# 2018_Dashboard.net
KiCad netlist of a schematic drawn in EAGLE
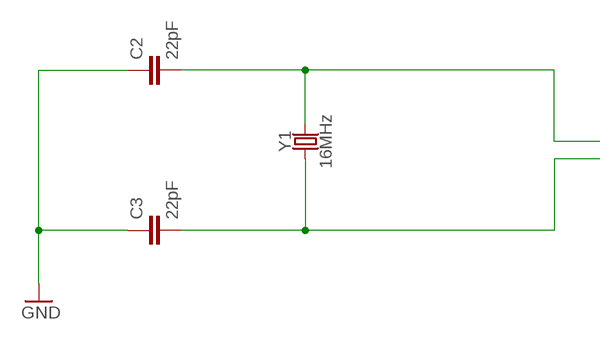
[diagram p0: schematic, sheet 1, part 1 of 2]
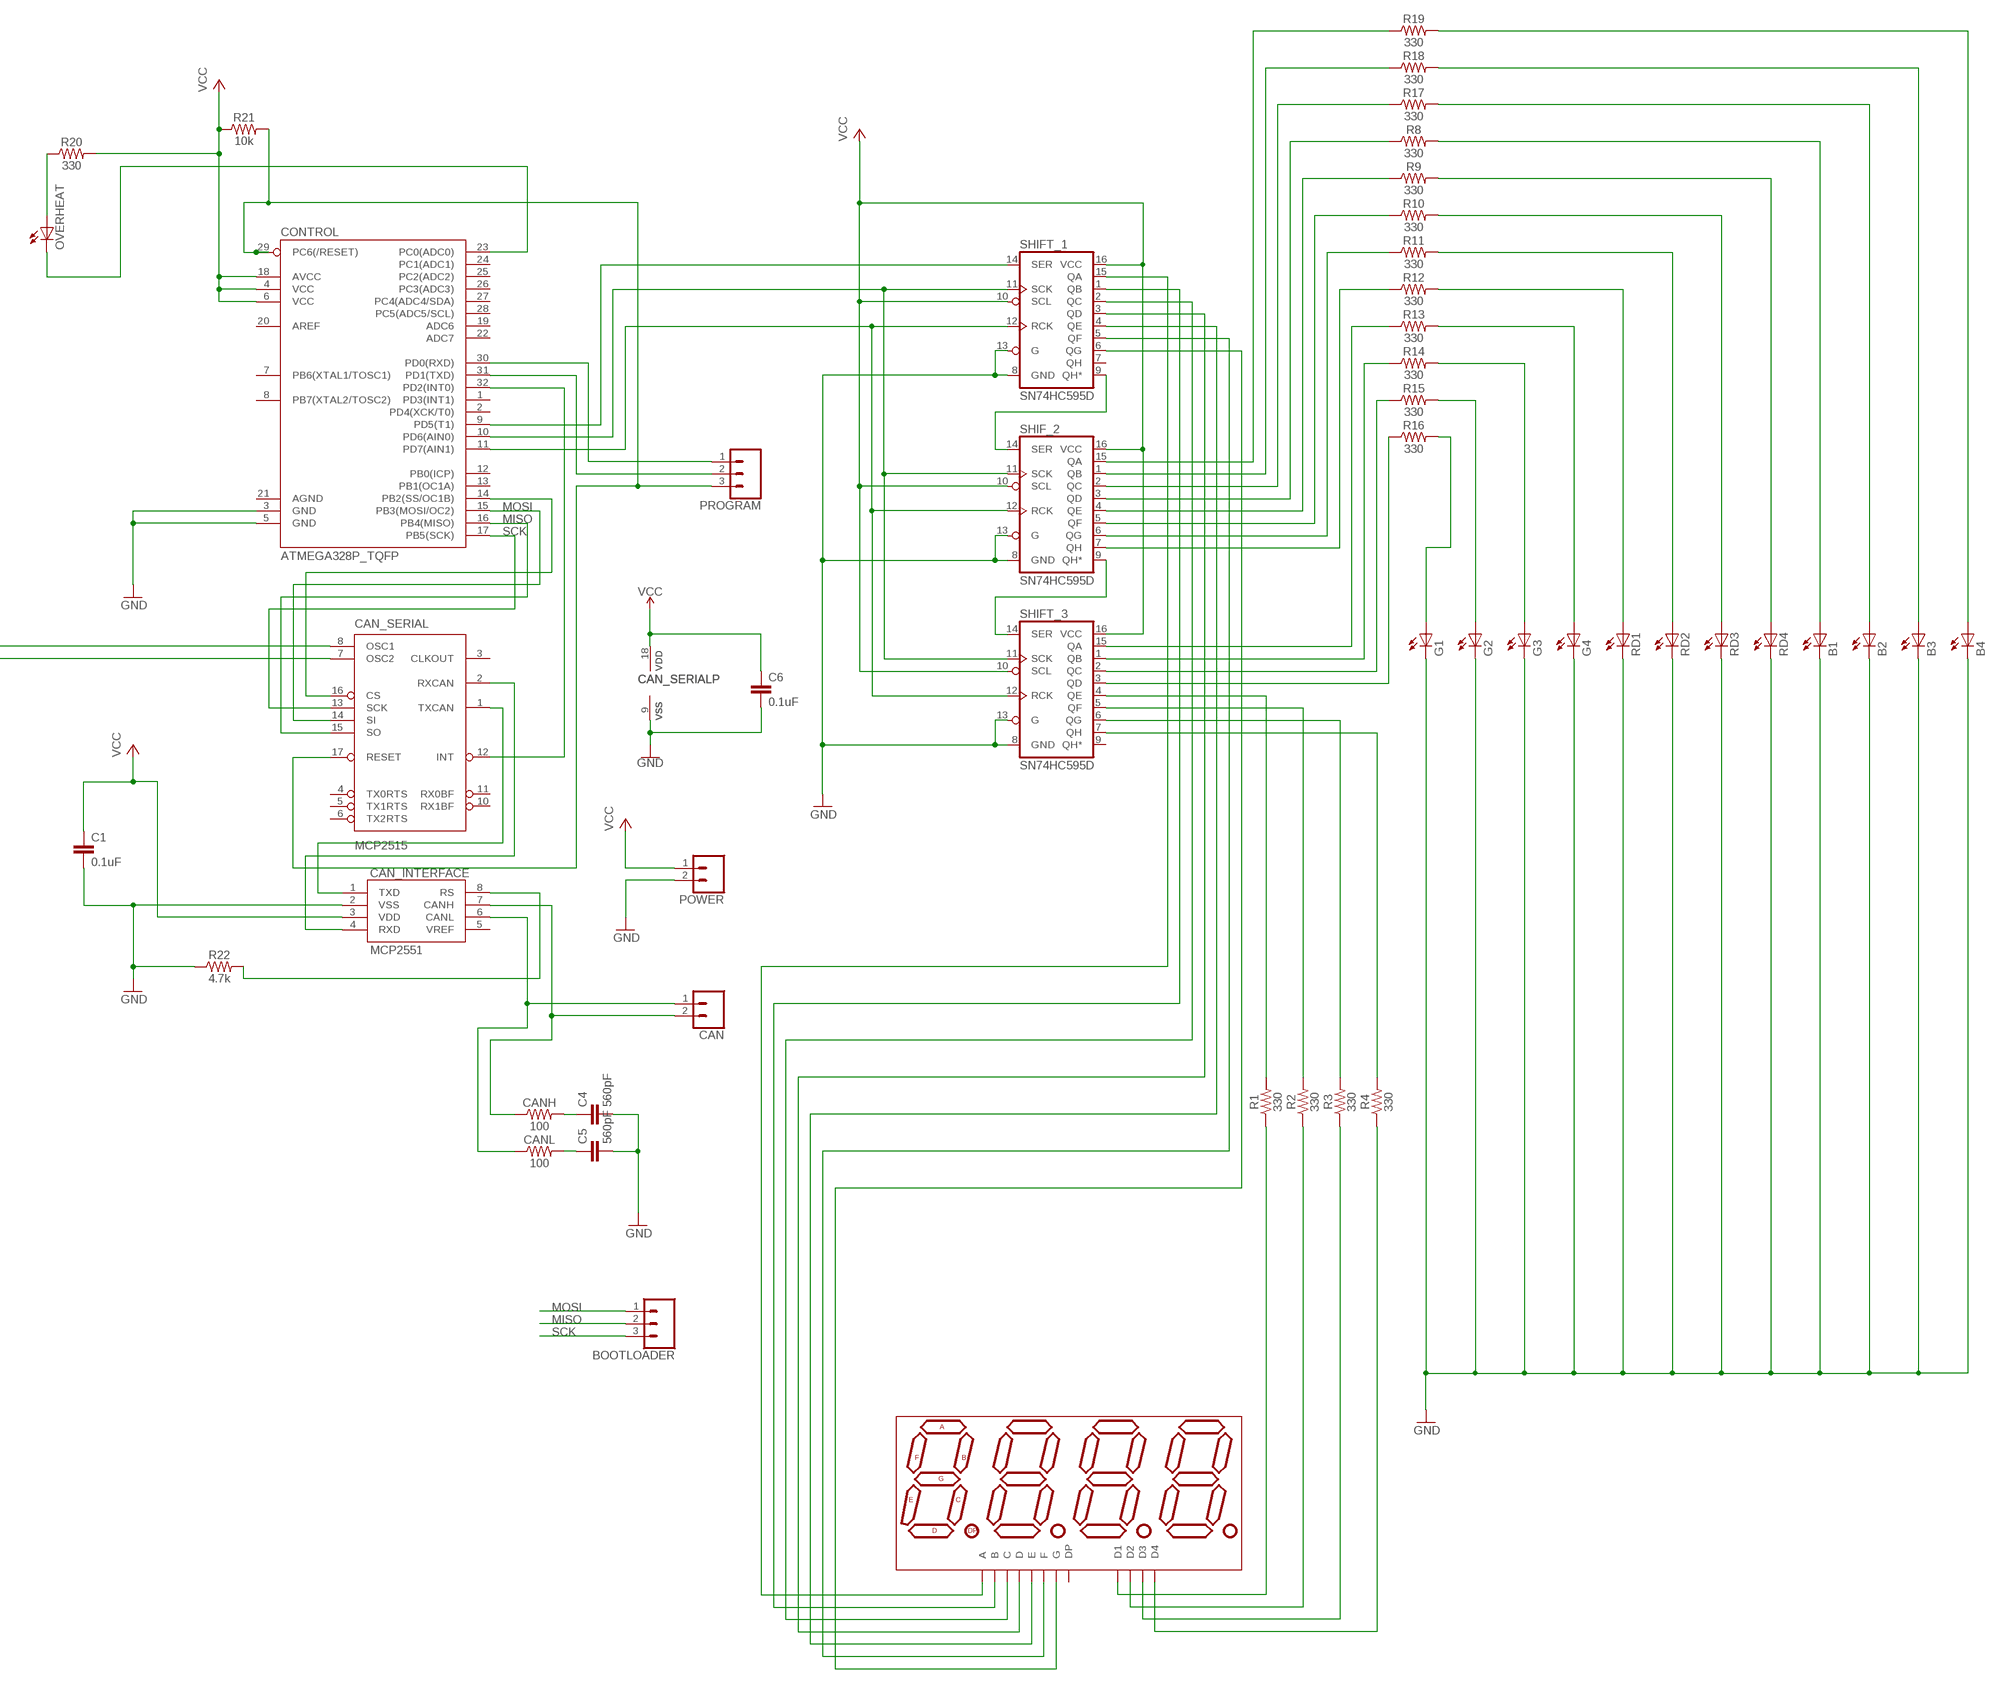
[diagram p1: schematic, sheet 1, part 2 of 2]

(export (version "E")
  (design (tool "Eeschema 10.0.6"))
  (components
    (comp (ref "B1")
      (value "TLLG4400")
      (footprint "eagle-import:LED3MM")
      (fields (field (name "MF") "VISHAY SEMICONDUCTOR"))
      (libsource (lib "eagle-import") (part "TLLG4400"))
    )
    (comp (ref "B2")
      (value "TLLG4400")
      (footprint "eagle-import:LED3MM")
      (fields (field (name "MF") "VISHAY SEMICONDUCTOR"))
      (libsource (lib "eagle-import") (part "TLLG4400"))
    )
    (comp (ref "B3")
      (value "TLLG4400")
      (footprint "eagle-import:LED3MM")
      (fields (field (name "MF") "VISHAY SEMICONDUCTOR"))
      (libsource (lib "eagle-import") (part "TLLG4400"))
    )
    (comp (ref "B4")
      (value "TLLG4400")
      (footprint "eagle-import:LED3MM")
      (fields (field (name "MF") "VISHAY SEMICONDUCTOR"))
      (libsource (lib "eagle-import") (part "TLLG4400"))
    )
    (comp (ref "BOOTLOADER")
      (value "CONN_03")
      (footprint "eagle-import:1X03")
      (libsource (lib "eagle-import") (part "CONN_03"))
    )
    (comp (ref "C1")
      (value "0.1uF")
      (footprint "eagle-import:0603")
      (libsource (lib "eagle-import") (part "0.1UF-0603-25V-(+80/-20%)"))
    )
    (comp (ref "C2")
      (value "22pF")
      (footprint "eagle-import:0603")
      (libsource (lib "eagle-import") (part "22PF-0603-50V-5%"))
    )
    (comp (ref "C3")
      (value "22pF")
      (footprint "eagle-import:0603")
      (libsource (lib "eagle-import") (part "22PF-0603-50V-5%"))
    )
    (comp (ref "C4")
      (value "560pF")
      (footprint "eagle-import:0603")
      (libsource (lib "eagle-import") (part "560PF-0603-50V-5%"))
    )
    (comp (ref "C5")
      (value "560pF")
      (footprint "eagle-import:0603")
      (libsource (lib "eagle-import") (part "560PF-0603-50V-5%"))
    )
    (comp (ref "C6")
      (value "0.1uF")
      (footprint "eagle-import:0402")
      (libsource (lib "eagle-import") (part "0.1UF-0402-16V-10%"))
    )
    (comp (ref "CAN")
      (value "CONN_02")
      (footprint "eagle-import:1X02")
      (libsource (lib "eagle-import") (part "CONN_02"))
    )
    (comp (ref "CANH")
      (value "100")
      (footprint "eagle-import:0603")
      (libsource (lib "eagle-import") (part "100OHM-0603-1/4W-5%"))
    )
    (comp (ref "CANL")
      (value "100")
      (footprint "eagle-import:0603")
      (libsource (lib "eagle-import") (part "100OHM-0603-1/4W-5%"))
    )
    (comp (ref "CAN_INTERFACE")
      (value "MCP2551")
      (footprint "eagle-import:SO08")
      (libsource (lib "eagle-import") (part "MCP2551"))
    )
    (comp (ref "CAN_SERIAL")
      (value "MCP2515")
      (footprint "eagle-import:SO18W")
      (libsource (lib "eagle-import") (part "MCP2515(MCP2510)SO"))
    )
    (comp (ref "CONTROL")
      (value "ATMEGA328P_TQFP")
      (footprint "eagle-import:TQFP32-08")
      (libsource (lib "eagle-import") (part "ATMEGA328P_TQFP"))
    )
    (comp (ref "G1")
      (value "TLLG4400")
      (footprint "eagle-import:LED3MM")
      (fields (field (name "MF") "VISHAY SEMICONDUCTOR"))
      (libsource (lib "eagle-import") (part "TLLG4400"))
    )
    (comp (ref "G2")
      (value "TLLG4400")
      (footprint "eagle-import:LED3MM")
      (fields (field (name "MF") "VISHAY SEMICONDUCTOR"))
      (libsource (lib "eagle-import") (part "TLLG4400"))
    )
    (comp (ref "G3")
      (value "TLLG4400")
      (footprint "eagle-import:LED3MM")
      (fields (field (name "MF") "VISHAY SEMICONDUCTOR"))
      (libsource (lib "eagle-import") (part "TLLG4400"))
    )
    (comp (ref "G4")
      (value "TLLG4400")
      (footprint "eagle-import:LED3MM")
      (fields (field (name "MF") "VISHAY SEMICONDUCTOR"))
      (libsource (lib "eagle-import") (part "TLLG4400"))
    )
    (comp (ref "OVERHEAT")
      (value "TLLG4400")
      (footprint "eagle-import:LED3MM")
      (fields (field (name "MF") "VISHAY SEMICONDUCTOR"))
      (libsource (lib "eagle-import") (part "TLLG4400"))
    )
    (comp (ref "POWER")
      (value "CONN_02")
      (footprint "eagle-import:1X02")
      (libsource (lib "eagle-import") (part "CONN_02"))
    )
    (comp (ref "PROGRAM")
      (value "CONN_03")
      (footprint "eagle-import:1X03")
      (libsource (lib "eagle-import") (part "CONN_03"))
    )
    (comp (ref "R1")
      (value "330")
      (footprint "eagle-import:0603")
      (libsource (lib "eagle-import") (part "330OHM-0603-1/10W-1%"))
    )
    (comp (ref "R2")
      (value "330")
      (footprint "eagle-import:0603")
      (libsource (lib "eagle-import") (part "330OHM-0603-1/10W-1%"))
    )
    (comp (ref "R3")
      (value "330")
      (footprint "eagle-import:0603")
      (libsource (lib "eagle-import") (part "330OHM-0603-1/10W-1%"))
    )
    (comp (ref "R4")
      (value "330")
      (footprint "eagle-import:0603")
      (libsource (lib "eagle-import") (part "330OHM-0603-1/10W-1%"))
    )
    (comp (ref "R8")
      (value "330")
      (footprint "eagle-import:0603")
      (libsource (lib "eagle-import") (part "330OHM-0603-1/10W-1%"))
    )
    (comp (ref "R9")
      (value "330")
      (footprint "eagle-import:0603")
      (libsource (lib "eagle-import") (part "330OHM-0603-1/10W-1%"))
    )
    (comp (ref "R10")
      (value "330")
      (footprint "eagle-import:0603")
      (libsource (lib "eagle-import") (part "330OHM-0603-1/10W-1%"))
    )
    (comp (ref "R11")
      (value "330")
      (footprint "eagle-import:0603")
      (libsource (lib "eagle-import") (part "330OHM-0603-1/10W-1%"))
    )
    (comp (ref "R12")
      (value "330")
      (footprint "eagle-import:0603")
      (libsource (lib "eagle-import") (part "330OHM-0603-1/10W-1%"))
    )
    (comp (ref "R13")
      (value "330")
      (footprint "eagle-import:0603")
      (libsource (lib "eagle-import") (part "330OHM-0603-1/10W-1%"))
    )
    (comp (ref "R14")
      (value "330")
      (footprint "eagle-import:0603")
      (libsource (lib "eagle-import") (part "330OHM-0603-1/10W-1%"))
    )
    (comp (ref "R15")
      (value "330")
      (footprint "eagle-import:0603")
      (libsource (lib "eagle-import") (part "330OHM-0603-1/10W-1%"))
    )
    (comp (ref "R16")
      (value "330")
      (footprint "eagle-import:0603")
      (libsource (lib "eagle-import") (part "330OHM-0603-1/10W-1%"))
    )
    (comp (ref "R17")
      (value "330")
      (footprint "eagle-import:0603")
      (libsource (lib "eagle-import") (part "330OHM-0603-1/10W-1%"))
    )
    (comp (ref "R18")
      (value "330")
      (footprint "eagle-import:0603")
      (libsource (lib "eagle-import") (part "330OHM-0603-1/10W-1%"))
    )
    (comp (ref "R19")
      (value "330")
      (footprint "eagle-import:0603")
      (libsource (lib "eagle-import") (part "330OHM-0603-1/10W-1%"))
    )
    (comp (ref "R20")
      (value "330")
      (footprint "eagle-import:0603")
      (libsource (lib "eagle-import") (part "330OHM-0603-1/10W-1%"))
    )
    (comp (ref "R21")
      (value "10k")
      (footprint "eagle-import:0603")
      (libsource (lib "eagle-import") (part "10KOHM-0603-1/10W-1%"))
    )
    (comp (ref "R22")
      (value "4.7k")
      (footprint "eagle-import:0603")
      (libsource (lib "eagle-import") (part "4.7KOHM-0603-1/10W-1%"))
    )
    (comp (ref "RD1")
      (value "TLLG4400")
      (footprint "eagle-import:LED3MM")
      (fields (field (name "MF") "VISHAY SEMICONDUCTOR"))
      (libsource (lib "eagle-import") (part "TLLG4400"))
    )
    (comp (ref "RD2")
      (value "TLLG4400")
      (footprint "eagle-import:LED3MM")
      (fields (field (name "MF") "VISHAY SEMICONDUCTOR"))
      (libsource (lib "eagle-import") (part "TLLG4400"))
    )
    (comp (ref "RD3")
      (value "TLLG4400")
      (footprint "eagle-import:LED3MM")
      (fields (field (name "MF") "VISHAY SEMICONDUCTOR"))
      (libsource (lib "eagle-import") (part "TLLG4400"))
    )
    (comp (ref "RD4")
      (value "TLLG4400")
      (footprint "eagle-import:LED3MM")
      (fields (field (name "MF") "VISHAY SEMICONDUCTOR"))
      (libsource (lib "eagle-import") (part "TLLG4400"))
    )
    (comp (ref "SEVEN_SEGMENT")
      (value "ATA8041AB")
      (footprint "eagle-import:7-SEGMENT-4DIGIT-20MM")
      (libsource (lib "eagle-import") (part "7-SEGMENT-4DIGIT-20MM-BLUE"))
    )
    (comp (ref "SHIFT_1")
      (value "SN74HC595D")
      (footprint "eagle-import:SO16")
      (libsource (lib "eagle-import") (part "74595DHC"))
    )
    (comp (ref "SHIFT_3")
      (value "SN74HC595D")
      (footprint "eagle-import:SO16")
      (libsource (lib "eagle-import") (part "74595DHC"))
    )
    (comp (ref "SHIF_2")
      (value "SN74HC595D")
      (footprint "eagle-import:SO16")
      (libsource (lib "eagle-import") (part "74595DHC"))
    )
    (comp (ref "Y1")
      (value "16MHz")
      (footprint "eagle-import:HC49US")
      (libsource (lib "eagle-import") (part "CRYSTAL-16MHZPTH-HC49US"))
    )
  )
  (nets
    (net (code "1") (name "/MISO") (class "Default")
      (node (ref "BOOTLOADER") (pin "2") (pinfunction "2_2") (pintype "passive"))
      (node (ref "CAN_SERIAL") (pin "15") (pinfunction "SO_15") (pintype "output"))
      (node (ref "CONTROL") (pin "16") (pinfunction "PB4(MISO)_16") (pintype "bidirectional"))
    )
    (net (code "2") (name "/MOSI") (class "Default")
      (node (ref "BOOTLOADER") (pin "1") (pinfunction "1_1") (pintype "passive"))
      (node (ref "CAN_SERIAL") (pin "14") (pinfunction "SI_14") (pintype "input"))
      (node (ref "CONTROL") (pin "15") (pinfunction "PB3(MOSI/OC2)_15") (pintype "bidirectional"))
    )
    (net (code "3") (name "/SCK") (class "Default")
      (node (ref "BOOTLOADER") (pin "3") (pinfunction "3_3") (pintype "passive"))
      (node (ref "CAN_SERIAL") (pin "13") (pinfunction "SCK_13") (pintype "input"))
      (node (ref "CONTROL") (pin "17") (pinfunction "PB5(SCK)_17") (pintype "bidirectional"))
    )
    (net (code "4") (name "GND") (class "Default")
      (node (ref "B1") (pin "K") (pinfunction "C_K") (pintype "passive"))
      (node (ref "B2") (pin "K") (pinfunction "C_K") (pintype "passive"))
      (node (ref "B3") (pin "K") (pinfunction "C_K") (pintype "passive"))
      (node (ref "B4") (pin "K") (pinfunction "C_K") (pintype "passive"))
      (node (ref "C1") (pin "2") (pinfunction "2_2") (pintype "passive"))
      (node (ref "C2") (pin "1") (pinfunction "1_1") (pintype "passive"))
      (node (ref "C3") (pin "1") (pinfunction "1_1") (pintype "passive"))
      (node (ref "C4") (pin "2") (pinfunction "2_2") (pintype "passive"))
      (node (ref "C5") (pin "2") (pinfunction "2_2") (pintype "passive"))
      (node (ref "C6") (pin "2") (pinfunction "2_2") (pintype "passive"))
      (node (ref "CAN_INTERFACE") (pin "2") (pinfunction "VSS_2") (pintype "bidirectional"))
      (node (ref "CAN_SERIAL") (pin "9") (pinfunction "VSS_9") (pintype "power_in"))
      (node (ref "CONTROL") (pin "3") (pinfunction "GND_3") (pintype "bidirectional"))
      (node (ref "CONTROL") (pin "5") (pinfunction "GND_5") (pintype "bidirectional"))
      (node (ref "G1") (pin "K") (pinfunction "C_K") (pintype "passive"))
      (node (ref "G2") (pin "K") (pinfunction "C_K") (pintype "passive"))
      (node (ref "G3") (pin "K") (pinfunction "C_K") (pintype "passive"))
      (node (ref "G4") (pin "K") (pinfunction "C_K") (pintype "passive"))
      (node (ref "POWER") (pin "2") (pinfunction "2_2") (pintype "passive"))
      (node (ref "R22") (pin "1") (pinfunction "1_1") (pintype "passive"))
      (node (ref "RD1") (pin "K") (pinfunction "C_K") (pintype "passive"))
      (node (ref "RD2") (pin "K") (pinfunction "C_K") (pintype "passive"))
      (node (ref "RD3") (pin "K") (pinfunction "C_K") (pintype "passive"))
      (node (ref "RD4") (pin "K") (pinfunction "C_K") (pintype "passive"))
      (node (ref "SHIFT_1") (pin "13") (pinfunction "G_13") (pintype "input"))
      (node (ref "SHIFT_1") (pin "8") (pinfunction "GND_8") (pintype "power_in"))
      (node (ref "SHIFT_3") (pin "13") (pinfunction "G_13") (pintype "input"))
      (node (ref "SHIFT_3") (pin "8") (pinfunction "GND_8") (pintype "power_in"))
      (node (ref "SHIF_2") (pin "13") (pinfunction "G_13") (pintype "input"))
      (node (ref "SHIF_2") (pin "8") (pinfunction "GND_8") (pintype "power_in"))
    )
    (net (code "5") (name "Net-(B1-PadA)") (class "Default")
      (node (ref "B1") (pin "A") (pinfunction "A_A") (pintype "passive"))
      (node (ref "R8") (pin "2") (pinfunction "2_2") (pintype "passive"))
    )
    (net (code "6") (name "Net-(B2-PadA)") (class "Default")
      (node (ref "B2") (pin "A") (pinfunction "A_A") (pintype "passive"))
      (node (ref "R17") (pin "2") (pinfunction "2_2") (pintype "passive"))
    )
    (net (code "7") (name "Net-(B3-PadA)") (class "Default")
      (node (ref "B3") (pin "A") (pinfunction "A_A") (pintype "passive"))
      (node (ref "R18") (pin "2") (pinfunction "2_2") (pintype "passive"))
    )
    (net (code "8") (name "Net-(B4-PadA)") (class "Default")
      (node (ref "B4") (pin "A") (pinfunction "A_A") (pintype "passive"))
      (node (ref "R19") (pin "2") (pinfunction "2_2") (pintype "passive"))
    )
    (net (code "9") (name "Net-(C4-Pad1)") (class "Default")
      (node (ref "C4") (pin "1") (pinfunction "1_1") (pintype "passive"))
      (node (ref "CANH") (pin "2") (pinfunction "2_2") (pintype "passive"))
    )
    (net (code "10") (name "Net-(C5-Pad1)") (class "Default")
      (node (ref "C5") (pin "1") (pinfunction "1_1") (pintype "passive"))
      (node (ref "CANL") (pin "2") (pinfunction "2_2") (pintype "passive"))
    )
    (net (code "11") (name "Net-(CAN_INTERFACE-CANH)") (class "Default")
      (node (ref "CAN") (pin "2") (pinfunction "2_2") (pintype "passive"))
      (node (ref "CANH") (pin "1") (pinfunction "1_1") (pintype "passive"))
      (node (ref "CAN_INTERFACE") (pin "7") (pinfunction "CANH_7") (pintype "bidirectional"))
    )
    (net (code "12") (name "Net-(CAN_INTERFACE-CANL)") (class "Default")
      (node (ref "CAN") (pin "1") (pinfunction "1_1") (pintype "passive"))
      (node (ref "CANL") (pin "1") (pinfunction "1_1") (pintype "passive"))
      (node (ref "CAN_INTERFACE") (pin "6") (pinfunction "CANL_6") (pintype "bidirectional"))
    )
    (net (code "13") (name "Net-(CAN_INTERFACE-RS)") (class "Default")
      (node (ref "CAN_INTERFACE") (pin "8") (pinfunction "RS_8") (pintype "bidirectional"))
      (node (ref "R22") (pin "2") (pinfunction "2_2") (pintype "passive"))
    )
    (net (code "14") (name "Net-(CAN_INTERFACE-RXD)") (class "Default")
      (node (ref "CAN_INTERFACE") (pin "4") (pinfunction "RXD_4") (pintype "bidirectional"))
      (node (ref "CAN_SERIAL") (pin "2") (pinfunction "RXCAN_2") (pintype "input"))
    )
    (net (code "15") (name "Net-(CAN_INTERFACE-TXD)") (class "Default")
      (node (ref "CAN_INTERFACE") (pin "1") (pinfunction "TXD_1") (pintype "bidirectional"))
      (node (ref "CAN_SERIAL") (pin "1") (pinfunction "TXCAN_1") (pintype "output"))
    )
    (net (code "16") (name "Net-(CAN_SERIALA-CS)") (class "Default")
      (node (ref "CAN_SERIAL") (pin "16") (pinfunction "CS_16") (pintype "input"))
      (node (ref "CONTROL") (pin "14") (pinfunction "PB2(SS/OC1B)_14") (pintype "bidirectional"))
    )
    (net (code "17") (name "Net-(CAN_SERIALA-INT)") (class "Default")
      (node (ref "CAN_SERIAL") (pin "12") (pinfunction "INT_12") (pintype "output"))
      (node (ref "CONTROL") (pin "32") (pinfunction "PD2(INT0)_32") (pintype "bidirectional"))
    )
    (net (code "18") (name "Net-(CAN_SERIALA-OSC1)") (class "Default")
      (node (ref "C2") (pin "2") (pinfunction "2_2") (pintype "passive"))
      (node (ref "CAN_SERIAL") (pin "8") (pinfunction "OSC1_8") (pintype "input"))
      (node (ref "Y1") (pin "2") (pinfunction "2_2") (pintype "passive"))
    )
    (net (code "19") (name "Net-(CAN_SERIALA-OSC2)") (class "Default")
      (node (ref "C3") (pin "2") (pinfunction "2_2") (pintype "passive"))
      (node (ref "CAN_SERIAL") (pin "7") (pinfunction "OSC2_7") (pintype "output"))
      (node (ref "Y1") (pin "1") (pinfunction "1_1") (pintype "passive"))
    )
    (net (code "20") (name "Net-(CAN_SERIALA-RESET)") (class "Default")
      (node (ref "CAN_SERIAL") (pin "17") (pinfunction "RESET_17") (pintype "input"))
      (node (ref "CONTROL") (pin "29") (pinfunction "PC6(/RESET)_29") (pintype "bidirectional"))
      (node (ref "PROGRAM") (pin "3") (pinfunction "3_3") (pintype "passive"))
      (node (ref "R21") (pin "2") (pinfunction "2_2") (pintype "passive"))
    )
    (net (code "21") (name "Net-(CONTROL-PC0(ADC0))") (class "Default")
      (node (ref "CONTROL") (pin "23") (pinfunction "PC0(ADC0)_23") (pintype "bidirectional"))
      (node (ref "OVERHEAT") (pin "K") (pinfunction "C_K") (pintype "passive"))
    )
    (net (code "22") (name "Net-(CONTROL-PD0(RXD))") (class "Default")
      (node (ref "CONTROL") (pin "30") (pinfunction "PD0(RXD)_30") (pintype "bidirectional"))
      (node (ref "PROGRAM") (pin "1") (pinfunction "1_1") (pintype "passive"))
    )
    (net (code "23") (name "Net-(CONTROL-PD1(TXD))") (class "Default")
      (node (ref "CONTROL") (pin "31") (pinfunction "PD1(TXD)_31") (pintype "bidirectional"))
      (node (ref "PROGRAM") (pin "2") (pinfunction "2_2") (pintype "passive"))
    )
    (net (code "24") (name "Net-(CONTROL-PD5(T1))") (class "Default")
      (node (ref "CONTROL") (pin "9") (pinfunction "PD5(T1)_9") (pintype "bidirectional"))
      (node (ref "SHIFT_1") (pin "14") (pinfunction "SER_14") (pintype "input"))
    )
    (net (code "25") (name "Net-(CONTROL-PD6(AIN0))") (class "Default")
      (node (ref "CONTROL") (pin "10") (pinfunction "PD6(AIN0)_10") (pintype "bidirectional"))
      (node (ref "SHIFT_1") (pin "11") (pinfunction "SCK_11") (pintype "input"))
      (node (ref "SHIFT_3") (pin "11") (pinfunction "SCK_11") (pintype "input"))
      (node (ref "SHIF_2") (pin "11") (pinfunction "SCK_11") (pintype "input"))
    )
    (net (code "26") (name "Net-(CONTROL-PD7(AIN1))") (class "Default")
      (node (ref "CONTROL") (pin "11") (pinfunction "PD7(AIN1)_11") (pintype "bidirectional"))
      (node (ref "SHIFT_1") (pin "12") (pinfunction "RCK_12") (pintype "input"))
      (node (ref "SHIFT_3") (pin "12") (pinfunction "RCK_12") (pintype "input"))
      (node (ref "SHIF_2") (pin "12") (pinfunction "RCK_12") (pintype "input"))
    )
    (net (code "27") (name "Net-(G1-PadA)") (class "Default")
      (node (ref "G1") (pin "A") (pinfunction "A_A") (pintype "passive"))
      (node (ref "R16") (pin "2") (pinfunction "2_2") (pintype "passive"))
    )
    (net (code "28") (name "Net-(G2-PadA)") (class "Default")
      (node (ref "G2") (pin "A") (pinfunction "A_A") (pintype "passive"))
      (node (ref "R15") (pin "2") (pinfunction "2_2") (pintype "passive"))
    )
    (net (code "29") (name "Net-(G3-PadA)") (class "Default")
      (node (ref "G3") (pin "A") (pinfunction "A_A") (pintype "passive"))
      (node (ref "R14") (pin "2") (pinfunction "2_2") (pintype "passive"))
    )
    (net (code "30") (name "Net-(G4-PadA)") (class "Default")
      (node (ref "G4") (pin "A") (pinfunction "A_A") (pintype "passive"))
      (node (ref "R13") (pin "2") (pinfunction "2_2") (pintype "passive"))
    )
    (net (code "31") (name "Net-(OVERHEAT-PadA)") (class "Default")
      (node (ref "OVERHEAT") (pin "A") (pinfunction "A_A") (pintype "passive"))
      (node (ref "R20") (pin "1") (pinfunction "1_1") (pintype "passive"))
    )
    (net (code "32") (name "Net-(R9-Pad2)") (class "Default")
      (node (ref "R9") (pin "2") (pinfunction "2_2") (pintype "passive"))
      (node (ref "RD4") (pin "A") (pinfunction "A_A") (pintype "passive"))
    )
    (net (code "33") (name "Net-(R10-Pad2)") (class "Default")
      (node (ref "R10") (pin "2") (pinfunction "2_2") (pintype "passive"))
      (node (ref "RD3") (pin "A") (pinfunction "A_A") (pintype "passive"))
    )
    (net (code "34") (name "Net-(R11-Pad2)") (class "Default")
      (node (ref "R11") (pin "2") (pinfunction "2_2") (pintype "passive"))
      (node (ref "RD2") (pin "A") (pinfunction "A_A") (pintype "passive"))
    )
    (net (code "35") (name "Net-(R12-Pad2)") (class "Default")
      (node (ref "R12") (pin "2") (pinfunction "2_2") (pintype "passive"))
      (node (ref "RD1") (pin "A") (pinfunction "A_A") (pintype "passive"))
    )
    (net (code "36") (name "Net-(SEVEN_SEGMENT-A)") (class "Default")
      (node (ref "SEVEN_SEGMENT") (pin "11") (pinfunction "A_11") (pintype "bidirectional"))
      (node (ref "SHIFT_1") (pin "15") (pinfunction "QA_15") (pintype "tri_state"))
    )
    (net (code "37") (name "Net-(SEVEN_SEGMENT-B)") (class "Default")
      (node (ref "SEVEN_SEGMENT") (pin "7") (pinfunction "B_7") (pintype "bidirectional"))
      (node (ref "SHIFT_1") (pin "1") (pinfunction "QB_1") (pintype "tri_state"))
    )
    (net (code "38") (name "Net-(SEVEN_SEGMENT-C)") (class "Default")
      (node (ref "SEVEN_SEGMENT") (pin "4") (pinfunction "C_4") (pintype "bidirectional"))
      (node (ref "SHIFT_1") (pin "2") (pinfunction "QC_2") (pintype "tri_state"))
    )
    (net (code "39") (name "Net-(SEVEN_SEGMENT-D)") (class "Default")
      (node (ref "SEVEN_SEGMENT") (pin "2") (pinfunction "D_2") (pintype "bidirectional"))
      (node (ref "SHIFT_1") (pin "3") (pinfunction "QD_3") (pintype "tri_state"))
    )
    (net (code "40") (name "Net-(SEVEN_SEGMENT-D1)") (class "Default")
      (node (ref "R1") (pin "1") (pinfunction "1_1") (pintype "passive"))
      (node (ref "SEVEN_SEGMENT") (pin "12") (pinfunction "D1_12") (pintype "bidirectional"))
    )
    (net (code "41") (name "Net-(SEVEN_SEGMENT-D2)") (class "Default")
      (node (ref "R2") (pin "1") (pinfunction "1_1") (pintype "passive"))
      (node (ref "SEVEN_SEGMENT") (pin "9") (pinfunction "D2_9") (pintype "bidirectional"))
    )
    (net (code "42") (name "Net-(SEVEN_SEGMENT-D3)") (class "Default")
      (node (ref "R3") (pin "1") (pinfunction "1_1") (pintype "passive"))
      (node (ref "SEVEN_SEGMENT") (pin "8") (pinfunction "D3_8") (pintype "bidirectional"))
    )
    (net (code "43") (name "Net-(SEVEN_SEGMENT-D4)") (class "Default")
      (node (ref "R4") (pin "1") (pinfunction "1_1") (pintype "passive"))
      (node (ref "SEVEN_SEGMENT") (pin "6") (pinfunction "D4_6") (pintype "bidirectional"))
    )
    (net (code "44") (name "Net-(SEVEN_SEGMENT-E)") (class "Default")
      (node (ref "SEVEN_SEGMENT") (pin "1") (pinfunction "E_1") (pintype "bidirectional"))
      (node (ref "SHIFT_1") (pin "4") (pinfunction "QE_4") (pintype "tri_state"))
    )
    (net (code "45") (name "Net-(SEVEN_SEGMENT-F)") (class "Default")
      (node (ref "SEVEN_SEGMENT") (pin "10") (pinfunction "F_10") (pintype "bidirectional"))
      (node (ref "SHIFT_1") (pin "5") (pinfunction "QF_5") (pintype "tri_state"))
    )
    (net (code "46") (name "Net-(SEVEN_SEGMENT-G)") (class "Default")
      (node (ref "SEVEN_SEGMENT") (pin "5") (pinfunction "G_5") (pintype "bidirectional"))
      (node (ref "SHIFT_1") (pin "6") (pinfunction "QG_6") (pintype "tri_state"))
    )
    (net (code "47") (name "Net-(SHIFT_1-QH*)") (class "Default")
      (node (ref "SHIFT_1") (pin "9") (pinfunction "QH*_9") (pintype "tri_state"))
      (node (ref "SHIF_2") (pin "14") (pinfunction "SER_14") (pintype "input"))
    )
    (net (code "48") (name "Net-(SHIFT_3-QA)") (class "Default")
      (node (ref "R13") (pin "1") (pinfunction "1_1") (pintype "passive"))
      (node (ref "SHIFT_3") (pin "15") (pinfunction "QA_15") (pintype "tri_state"))
    )
    (net (code "49") (name "Net-(SHIFT_3-QB)") (class "Default")
      (node (ref "R14") (pin "1") (pinfunction "1_1") (pintype "passive"))
      (node (ref "SHIFT_3") (pin "1") (pinfunction "QB_1") (pintype "tri_state"))
    )
    (net (code "50") (name "Net-(SHIFT_3-QC)") (class "Default")
      (node (ref "R15") (pin "1") (pinfunction "1_1") (pintype "passive"))
      (node (ref "SHIFT_3") (pin "2") (pinfunction "QC_2") (pintype "tri_state"))
    )
    (net (code "51") (name "Net-(SHIFT_3-QD)") (class "Default")
      (node (ref "R16") (pin "1") (pinfunction "1_1") (pintype "passive"))
      (node (ref "SHIFT_3") (pin "3") (pinfunction "QD_3") (pintype "tri_state"))
    )
    (net (code "52") (name "Net-(SHIFT_3-QE)") (class "Default")
      (node (ref "R1") (pin "2") (pinfunction "2_2") (pintype "passive"))
      (node (ref "SHIFT_3") (pin "4") (pinfunction "QE_4") (pintype "tri_state"))
    )
    (net (code "53") (name "Net-(SHIFT_3-QF)") (class "Default")
      (node (ref "R2") (pin "2") (pinfunction "2_2") (pintype "passive"))
      (node (ref "SHIFT_3") (pin "5") (pinfunction "QF_5") (pintype "tri_state"))
    )
    (net (code "54") (name "Net-(SHIFT_3-QG)") (class "Default")
      (node (ref "R3") (pin "2") (pinfunction "2_2") (pintype "passive"))
      (node (ref "SHIFT_3") (pin "6") (pinfunction "QG_6") (pintype "tri_state"))
    )
    (net (code "55") (name "Net-(SHIFT_3-QH)") (class "Default")
      (node (ref "R4") (pin "2") (pinfunction "2_2") (pintype "passive"))
      (node (ref "SHIFT_3") (pin "7") (pinfunction "QH_7") (pintype "tri_state"))
    )
    (net (code "56") (name "Net-(SHIFT_3-SER)") (class "Default")
      (node (ref "SHIFT_3") (pin "14") (pinfunction "SER_14") (pintype "input"))
      (node (ref "SHIF_2") (pin "9") (pinfunction "QH*_9") (pintype "tri_state"))
    )
    (net (code "57") (name "Net-(SHIF_2-QA)") (class "Default")
      (node (ref "R19") (pin "1") (pinfunction "1_1") (pintype "passive"))
      (node (ref "SHIF_2") (pin "15") (pinfunction "QA_15") (pintype "tri_state"))
    )
    (net (code "58") (name "Net-(SHIF_2-QB)") (class "Default")
      (node (ref "R18") (pin "1") (pinfunction "1_1") (pintype "passive"))
      (node (ref "SHIF_2") (pin "1") (pinfunction "QB_1") (pintype "tri_state"))
    )
    (net (code "59") (name "Net-(SHIF_2-QC)") (class "Default")
      (node (ref "R17") (pin "1") (pinfunction "1_1") (pintype "passive"))
      (node (ref "SHIF_2") (pin "2") (pinfunction "QC_2") (pintype "tri_state"))
    )
    (net (code "60") (name "Net-(SHIF_2-QD)") (class "Default")
      (node (ref "R8") (pin "1") (pinfunction "1_1") (pintype "passive"))
      (node (ref "SHIF_2") (pin "3") (pinfunction "QD_3") (pintype "tri_state"))
    )
    (net (code "61") (name "Net-(SHIF_2-QE)") (class "Default")
      (node (ref "R9") (pin "1") (pinfunction "1_1") (pintype "passive"))
      (node (ref "SHIF_2") (pin "4") (pinfunction "QE_4") (pintype "tri_state"))
    )
    (net (code "62") (name "Net-(SHIF_2-QF)") (class "Default")
      (node (ref "R10") (pin "1") (pinfunction "1_1") (pintype "passive"))
      (node (ref "SHIF_2") (pin "5") (pinfunction "QF_5") (pintype "tri_state"))
    )
    (net (code "63") (name "Net-(SHIF_2-QG)") (class "Default")
      (node (ref "R11") (pin "1") (pinfunction "1_1") (pintype "passive"))
      (node (ref "SHIF_2") (pin "6") (pinfunction "QG_6") (pintype "tri_state"))
    )
    (net (code "64") (name "Net-(SHIF_2-QH)") (class "Default")
      (node (ref "R12") (pin "1") (pinfunction "1_1") (pintype "passive"))
      (node (ref "SHIF_2") (pin "7") (pinfunction "QH_7") (pintype "tri_state"))
    )
    (net (code "65") (name "VCC") (class "Default")
      (node (ref "C1") (pin "1") (pinfunction "1_1") (pintype "passive"))
      (node (ref "C6") (pin "1") (pinfunction "1_1") (pintype "passive"))
      (node (ref "CAN_INTERFACE") (pin "3") (pinfunction "VDD_3") (pintype "bidirectional"))
      (node (ref "CAN_SERIAL") (pin "18") (pinfunction "VDD_18") (pintype "power_in"))
      (node (ref "CONTROL") (pin "18") (pinfunction "AVCC_18") (pintype "bidirectional"))
      (node (ref "CONTROL") (pin "4") (pinfunction "VCC_4") (pintype "bidirectional"))
      (node (ref "CONTROL") (pin "6") (pinfunction "VCC_6") (pintype "bidirectional"))
      (node (ref "POWER") (pin "1") (pinfunction "1_1") (pintype "passive"))
      (node (ref "R20") (pin "2") (pinfunction "2_2") (pintype "passive"))
      (node (ref "R21") (pin "1") (pinfunction "1_1") (pintype "passive"))
      (node (ref "SHIFT_1") (pin "10") (pinfunction "SCL_10") (pintype "input"))
      (node (ref "SHIFT_1") (pin "16") (pinfunction "VCC_16") (pintype "power_in"))
      (node (ref "SHIFT_3") (pin "10") (pinfunction "SCL_10") (pintype "input"))
      (node (ref "SHIFT_3") (pin "16") (pinfunction "VCC_16") (pintype "power_in"))
      (node (ref "SHIF_2") (pin "10") (pinfunction "SCL_10") (pintype "input"))
      (node (ref "SHIF_2") (pin "16") (pinfunction "VCC_16") (pintype "power_in"))
    )
    (net (code "66") (name "unconnected-(CAN_INTERFACE-VREF-Pad5)") (class "Default")
      (node (ref "CAN_INTERFACE") (pin "5") (pinfunction "VREF_5") (pintype "bidirectional"))
    )
    (net (code "67") (name "unconnected-(CAN_SERIALA-CLKOUT-Pad3)") (class "Default")
      (node (ref "CAN_SERIAL") (pin "3") (pinfunction "CLKOUT_3") (pintype "output"))
    )
    (net (code "68") (name "unconnected-(CAN_SERIALA-RX0BF-Pad11)") (class "Default")
      (node (ref "CAN_SERIAL") (pin "11") (pinfunction "RX0BF_11") (pintype "output"))
    )
    (net (code "69") (name "unconnected-(CAN_SERIALA-RX1BF-Pad10)") (class "Default")
      (node (ref "CAN_SERIAL") (pin "10") (pinfunction "RX1BF_10") (pintype "output"))
    )
    (net (code "70") (name "unconnected-(CAN_SERIALA-TX0RTS-Pad4)") (class "Default")
      (node (ref "CAN_SERIAL") (pin "4") (pinfunction "TX0RTS_4") (pintype "input"))
    )
    (net (code "71") (name "unconnected-(CAN_SERIALA-TX1RTS-Pad5)") (class "Default")
      (node (ref "CAN_SERIAL") (pin "5") (pinfunction "TX1RTS_5") (pintype "input"))
    )
    (net (code "72") (name "unconnected-(CAN_SERIALA-TX2RTS-Pad6)") (class "Default")
      (node (ref "CAN_SERIAL") (pin "6") (pinfunction "TX2RTS_6") (pintype "input"))
    )
    (net (code "73") (name "unconnected-(CONTROL-ADC6-Pad19)") (class "Default")
      (node (ref "CONTROL") (pin "19") (pinfunction "ADC6_19") (pintype "bidirectional"))
    )
    (net (code "74") (name "unconnected-(CONTROL-ADC7-Pad22)") (class "Default")
      (node (ref "CONTROL") (pin "22") (pinfunction "ADC7_22") (pintype "bidirectional"))
    )
    (net (code "75") (name "unconnected-(CONTROL-AGND-Pad21)") (class "Default")
      (node (ref "CONTROL") (pin "21") (pinfunction "AGND_21") (pintype "bidirectional"))
    )
    (net (code "76") (name "unconnected-(CONTROL-AREF-Pad20)") (class "Default")
      (node (ref "CONTROL") (pin "20") (pinfunction "AREF_20") (pintype "bidirectional"))
    )
    (net (code "77") (name "unconnected-(CONTROL-PB0(ICP)-Pad12)") (class "Default")
      (node (ref "CONTROL") (pin "12") (pinfunction "PB0(ICP)_12") (pintype "bidirectional"))
    )
    (net (code "78") (name "unconnected-(CONTROL-PB1(OC1A)-Pad13)") (class "Default")
      (node (ref "CONTROL") (pin "13") (pinfunction "PB1(OC1A)_13") (pintype "bidirectional"))
    )
    (net (code "79") (name "unconnected-(CONTROL-PB6(XTAL1{slash}TOSC1)-Pad7)") (class "Default")
      (node (ref "CONTROL") (pin "7") (pinfunction "PB6(XTAL1/TOSC1)_7") (pintype "bidirectional"))
    )
    (net (code "80") (name "unconnected-(CONTROL-PB7(XTAL2{slash}TOSC2)-Pad8)") (class "Default")
      (node (ref "CONTROL") (pin "8") (pinfunction "PB7(XTAL2/TOSC2)_8") (pintype "bidirectional"))
    )
    (net (code "81") (name "unconnected-(CONTROL-PC1(ADC1)-Pad24)") (class "Default")
      (node (ref "CONTROL") (pin "24") (pinfunction "PC1(ADC1)_24") (pintype "bidirectional"))
    )
    (net (code "82") (name "unconnected-(CONTROL-PC2(ADC2)-Pad25)") (class "Default")
      (node (ref "CONTROL") (pin "25") (pinfunction "PC2(ADC2)_25") (pintype "bidirectional"))
    )
    (net (code "83") (name "unconnected-(CONTROL-PC3(ADC3)-Pad26)") (class "Default")
      (node (ref "CONTROL") (pin "26") (pinfunction "PC3(ADC3)_26") (pintype "bidirectional"))
    )
    (net (code "84") (name "unconnected-(CONTROL-PC4(ADC4{slash}SDA)-Pad27)") (class "Default")
      (node (ref "CONTROL") (pin "27") (pinfunction "PC4(ADC4/SDA)_27") (pintype "bidirectional"))
    )
    (net (code "85") (name "unconnected-(CONTROL-PC5(ADC5{slash}SCL)-Pad28)") (class "Default")
      (node (ref "CONTROL") (pin "28") (pinfunction "PC5(ADC5/SCL)_28") (pintype "bidirectional"))
    )
    (net (code "86") (name "unconnected-(CONTROL-PD3(INT1)-Pad1)") (class "Default")
      (node (ref "CONTROL") (pin "1") (pinfunction "PD3(INT1)_1") (pintype "bidirectional"))
    )
    (net (code "87") (name "unconnected-(CONTROL-PD4(XCK{slash}T0)-Pad2)") (class "Default")
      (node (ref "CONTROL") (pin "2") (pinfunction "PD4(XCK/T0)_2") (pintype "bidirectional"))
    )
    (net (code "88") (name "unconnected-(SEVEN_SEGMENT-DP-Pad3)") (class "Default")
      (node (ref "SEVEN_SEGMENT") (pin "3") (pinfunction "DP_3") (pintype "bidirectional"))
    )
    (net (code "89") (name "unconnected-(SHIFT_1-QH-Pad7)") (class "Default")
      (node (ref "SHIFT_1") (pin "7") (pinfunction "QH_7") (pintype "tri_state"))
    )
    (net (code "90") (name "unconnected-(SHIFT_3-QH*-Pad9)") (class "Default")
      (node (ref "SHIFT_3") (pin "9") (pinfunction "QH*_9") (pintype "tri_state"))
    )
  )
)
